# 3_3V3LDO.net
KiCad netlist of a schematic drawn in Altium Designer
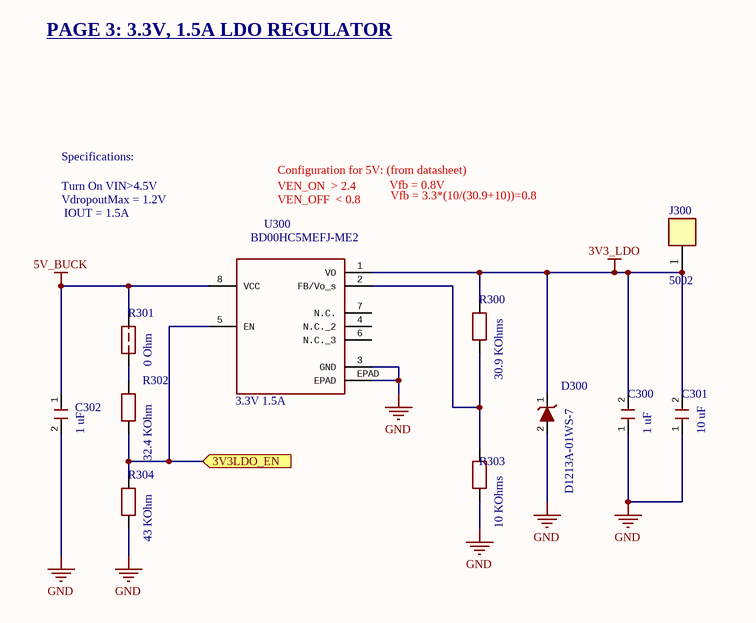
[diagram p0: 3_3V3LDO.SchDoc]

(export (version "E")
  (design (tool "Eeschema 10.0.6"))
  (components
    (comp (ref "C300")
      (value "1 uF")
      (footprint "CAP_0603")
      (description "Cap Ceramic 1uF 16V 0603")
      (fields
        (field (name "MANUFACTURER_PART_NUMBER") "GCM188R71C105KA64D")
        (field (name "MOUSER_PART_NUMBER") "81-GCM188R71C105K64D")
      )
      (libsource (lib "Passives") (part "GCM188R71C105KA64D"))
    )
    (comp (ref "C301")
      (value "10 uF")
      (footprint "CAP_0603")
      (description "Cap Ceramic 10uF 35V 0603")
      (fields (field (name "PARTNUMBER") "GRM188R61E106KA73D"))
      (libsource (lib "Passives") (part "GRM188R61E106KA73D"))
    )
    (comp (ref "C302")
      (value "1 uF")
      (footprint "CAP_0603")
      (description "Cap Ceramic 1uF 50V 0603")
      (fields
        (field (name "MANUFACTURER") "Murata Electronics")
        (field (name "PARTNUMBER") "GCM188R71C105KA64")
      )
      (libsource (lib "Passives") (part "GRT188R61H105KE13D"))
    )
    (comp (ref "D300")
      (value "D1213A-01WS-7")
      (footprint "DIODE_DO-214AC")
      (description "Diode TVS 3V3")
      (fields (field (name "MANUFACTURER") "Diodes Inc"))
      (libsource (lib "Passives") (part "D1213A-01WS-7"))
    )
    (comp (ref "J300")
      (value "5002")
      (footprint "Miscellaneous:KEYSTONE_5002")
      (description "Test Point Ring Keystone")
      (fields (field (name "MANUFACTURER") "Keystone Electronics"))
      (libsource (lib "Miscellaneous") (part "5002"))
    )
    (comp (ref "R300")
      (value "30.9 KOhms")
      (footprint "RES_0603")
      (description "Res 30.9KOhms 1/8W 0603")
      (fields (field (name "PARTNUMBER") "ERJ6ENF3092V"))
      (libsource (lib "Passives") (part "ERJ6ENF3092V"))
    )
    (comp (ref "R301")
      (value "0 Ohm")
      (footprint "RES_0603")
      (description "Res 0Ohm 1/10W 0603")
      (fields (field (name "PARTNUMBER") "ERJ3GEY0R00V"))
      (libsource (lib "Passives") (part "ERJ3GEY0R00V"))
    )
    (comp (ref "R302")
      (value "32.4 KOhm")
      (footprint "RES_0603")
      (description "Res 32.4KOhm 1/10W 0603")
      (fields (field (name "PARTNUMBER") "RC0603FR-0732K4L"))
      (libsource (lib "Passives") (part "RC0603FR-0732K4L"))
    )
    (comp (ref "R303")
      (value "10 KOhms")
      (footprint "RES_0603")
      (description "Res 10KOhms 1/10W 0603")
      (fields (field (name "PARTNUMBER") "ERJ3GEYJ103V"))
      (libsource (lib "Passives") (part "ERJ3GEYJ103V"))
    )
    (comp (ref "R304")
      (value "43 KOhm")
      (footprint "RES_0603")
      (description "Res 43KOhm 1/10W 0603")
      (fields (field (name "PARTNUMBER") "ERJ3GEYJ433V"))
      (libsource (lib "Passives") (part "ERJ3GEYJ433V"))
    )
    (comp (ref "U300")
      (value "BD00HC5MEFJ-ME2")
      (footprint "REG_SOP8_SOIC8_EPAD")
      (description "LDO 5Vin 3V3Out 1.5A")
      (fields (field (name "MANUFACTURER") "ROHM Semiconductor") (field (name "ALTIUM_VALUE") "3.3V 1.5A"))
      (libsource (lib "Regulators") (part "BD00HC5MEFJ-ME2"))
    )
  )
  (nets
    (net (code "1") (name "/3V3LDO_EN") (class "Default")
      (node (ref "R302") (pin "2") (pinfunction "2_2") (pintype "passive"))
      (node (ref "R304") (pin "2") (pinfunction "2_2") (pintype "passive"))
      (node (ref "U300") (pin "5") (pinfunction "EN_5") (pintype "passive"))
    )
    (net (code "2") (name "3V3_LDO") (class "Default")
      (node (ref "C300") (pin "2") (pinfunction "2_2") (pintype "passive"))
      (node (ref "C301") (pin "2") (pinfunction "2_2") (pintype "passive"))
      (node (ref "D300") (pin "1") (pinfunction "1_1") (pintype "passive"))
      (node (ref "J300") (pin "1") (pintype "passive"))
      (node (ref "R300") (pin "2") (pinfunction "2_2") (pintype "passive"))
      (node (ref "U300") (pin "1") (pinfunction "VO_1") (pintype "passive"))
    )
    (net (code "3") (name "5V_BUCK") (class "Default")
      (node (ref "C302") (pin "1") (pinfunction "1_1") (pintype "passive"))
      (node (ref "R301") (pin "2") (pinfunction "2_2") (pintype "passive"))
      (node (ref "U300") (pin "8") (pinfunction "VCC_8") (pintype "power_in"))
    )
    (net (code "4") (name "GND") (class "Default")
      (node (ref "C300") (pin "1") (pinfunction "1_1") (pintype "passive"))
      (node (ref "C301") (pin "1") (pinfunction "1_1") (pintype "passive"))
      (node (ref "C302") (pin "2") (pinfunction "2_2") (pintype "passive"))
      (node (ref "D300") (pin "2") (pinfunction "2_2") (pintype "passive"))
      (node (ref "R303") (pin "1") (pinfunction "1_1") (pintype "passive"))
      (node (ref "R304") (pin "1") (pinfunction "1_1") (pintype "passive"))
      (node (ref "U300") (pin "3") (pinfunction "GND_3") (pintype "passive"))
      (node (ref "U300") (pin "EPAD") (pinfunction "EPAD_EPAD") (pintype "passive"))
    )
    (net (code "5") (name "Net-(R301-Pad1)") (class "Default")
      (node (ref "R301") (pin "1") (pinfunction "1_1") (pintype "passive"))
      (node (ref "R302") (pin "1") (pinfunction "1_1") (pintype "passive"))
    )
    (net (code "6") (name "Net-(U300-FB{slash}Vo_s)") (class "Default")
      (node (ref "R300") (pin "1") (pinfunction "1_1") (pintype "passive"))
      (node (ref "R303") (pin "2") (pinfunction "2_2") (pintype "passive"))
      (node (ref "U300") (pin "2") (pinfunction "FB/Vo_s_2") (pintype "passive"))
    )
    (net (code "7") (name "unconnected-(U300-N.C.-Pad7)") (class "Default")
      (node (ref "U300") (pin "7") (pinfunction "N.C._7") (pintype "passive"))
    )
    (net (code "8") (name "unconnected-(U300-N.C._2-Pad4)") (class "Default")
      (node (ref "U300") (pin "4") (pinfunction "N.C._2_4") (pintype "passive"))
    )
    (net (code "9") (name "unconnected-(U300-N.C._3-Pad6)") (class "Default")
      (node (ref "U300") (pin "6") (pinfunction "N.C._3_6") (pintype "passive"))
    )
  )
)
